# BMU_control.net
KiCad netlist of a schematic drawn in Altium Designer
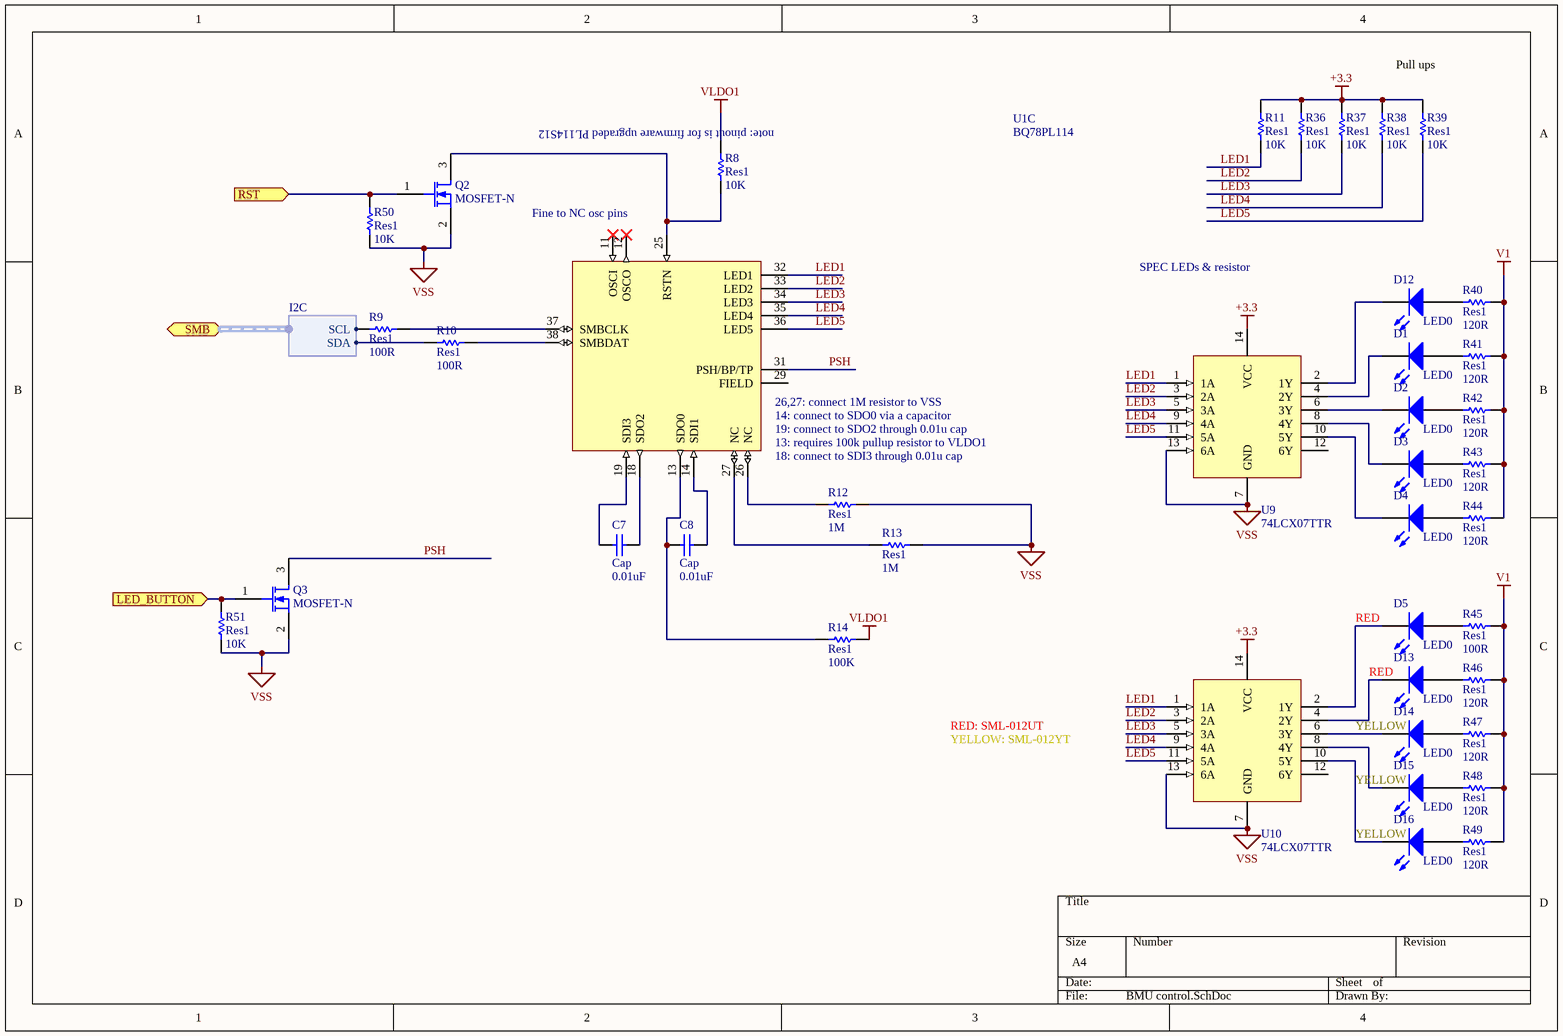
[diagram p0: BMU control.SchDoc]

(export (version "E")
  (design (tool "Eeschema 10.0.6"))
  (components
    (comp (ref "C7")
      (value "Cap")
      (footprint "C0805")
      (description "Capacitor")
      (fields (field (name "ALTIUM_VALUE") "0.01uF") (field (name "PUBLISHER") "Altium Limited"))
      (libsource (lib "Miscellaneous Devices") (part "Cap"))
    )
    (comp (ref "C8")
      (value "Cap")
      (footprint "C0805")
      (description "Capacitor")
      (fields (field (name "ALTIUM_VALUE") "0.01uF") (field (name "PUBLISHER") "Altium Limited"))
      (libsource (lib "Miscellaneous Devices") (part "Cap"))
    )
    (comp (ref "D1")
      (value "LED0")
      (footprint "SML-01 (ROHM LED SERIES)")
      (fields (field (name "PUBLISHER") "Altium Limited"))
      (libsource (lib "Miscellaneous Devices") (part "LED0"))
    )
    (comp (ref "D2")
      (value "LED0")
      (footprint "SML-01 (ROHM LED SERIES)")
      (fields (field (name "PUBLISHER") "Altium Limited"))
      (libsource (lib "Miscellaneous Devices") (part "LED0"))
    )
    (comp (ref "D3")
      (value "LED0")
      (footprint "SML-01 (ROHM LED SERIES)")
      (fields (field (name "PUBLISHER") "Altium Limited"))
      (libsource (lib "Miscellaneous Devices") (part "LED0"))
    )
    (comp (ref "D4")
      (value "LED0")
      (footprint "SML-01 (ROHM LED SERIES)")
      (fields (field (name "PUBLISHER") "Altium Limited"))
      (libsource (lib "Miscellaneous Devices") (part "LED0"))
    )
    (comp (ref "D5")
      (value "LED0")
      (footprint "SML-01 (ROHM LED SERIES)")
      (fields (field (name "COLOUR") "RED") (field (name "PUBLISHER") "Altium Limited"))
      (libsource (lib "Miscellaneous Devices") (part "LED0"))
    )
    (comp (ref "D12")
      (value "LED0")
      (footprint "SML-01 (ROHM LED SERIES)")
      (fields (field (name "PUBLISHER") "Altium Limited"))
      (libsource (lib "Miscellaneous Devices") (part "LED0"))
    )
    (comp (ref "D13")
      (value "LED0")
      (footprint "SML-01 (ROHM LED SERIES)")
      (fields (field (name "COLOUR") "RED") (field (name "PUBLISHER") "Altium Limited"))
      (libsource (lib "Miscellaneous Devices") (part "LED0"))
    )
    (comp (ref "D14")
      (value "LED0")
      (footprint "SML-01 (ROHM LED SERIES)")
      (fields (field (name "COLOUR") "YELLOW") (field (name "PUBLISHER") "Altium Limited"))
      (libsource (lib "Miscellaneous Devices") (part "LED0"))
    )
    (comp (ref "D15")
      (value "LED0")
      (footprint "SML-01 (ROHM LED SERIES)")
      (fields (field (name "COLOUR") "YELLOW") (field (name "PUBLISHER") "Altium Limited"))
      (libsource (lib "Miscellaneous Devices") (part "LED0"))
    )
    (comp (ref "D16")
      (value "LED0")
      (footprint "SML-01 (ROHM LED SERIES)")
      (fields (field (name "COLOUR") "YELLOW") (field (name "PUBLISHER") "Altium Limited"))
      (libsource (lib "Miscellaneous Devices") (part "LED0"))
    )
    (comp (ref "Q2")
      (value "MOSFET-N")
      (footprint "2N7002")
      (description "NXP - 2N7002 - MOSFET,N CH, 60V,0.3A,SOT23")
      (libsource (lib "2N7002") (part "2N7002"))
    )
    (comp (ref "Q3")
      (value "MOSFET-N")
      (footprint "2N7002")
      (description "NXP - 2N7002 - MOSFET,N CH, 60V,0.3A,SOT23")
      (libsource (lib "2N7002") (part "2N7002"))
    )
    (comp (ref "R8")
      (value "Res1")
      (footprint "R0603")
      (description "Resistor")
      (fields (field (name "ALTIUM_VALUE") "10K") (field (name "PUBLISHER") "Altium Limited"))
      (libsource (lib "Miscellaneous Devices") (part "Res1"))
    )
    (comp (ref "R9")
      (value "Res1")
      (footprint "R0603")
      (description "Resistor")
      (fields (field (name "ALTIUM_VALUE") "100R") (field (name "PUBLISHER") "Altium Limited"))
      (libsource (lib "Miscellaneous Devices") (part "Res1"))
    )
    (comp (ref "R10")
      (value "Res1")
      (footprint "R0603")
      (description "Resistor")
      (fields (field (name "ALTIUM_VALUE") "100R") (field (name "PUBLISHER") "Altium Limited"))
      (libsource (lib "Miscellaneous Devices") (part "Res1"))
    )
    (comp (ref "R11")
      (value "Res1")
      (footprint "R0603")
      (description "Resistor")
      (fields (field (name "ALTIUM_VALUE") "10K") (field (name "PUBLISHER") "Altium Limited"))
      (libsource (lib "Miscellaneous Devices") (part "Res1"))
    )
    (comp (ref "R12")
      (value "Res1")
      (footprint "R0603")
      (description "Resistor")
      (fields (field (name "ALTIUM_VALUE") "1M") (field (name "PUBLISHER") "Altium Limited"))
      (libsource (lib "Miscellaneous Devices") (part "Res1"))
    )
    (comp (ref "R13")
      (value "Res1")
      (footprint "R0603")
      (description "Resistor")
      (fields (field (name "ALTIUM_VALUE") "1M") (field (name "PUBLISHER") "Altium Limited"))
      (libsource (lib "Miscellaneous Devices") (part "Res1"))
    )
    (comp (ref "R14")
      (value "Res1")
      (footprint "R0603")
      (description "Resistor")
      (fields (field (name "ALTIUM_VALUE") "100K") (field (name "PUBLISHER") "Altium Limited"))
      (libsource (lib "Miscellaneous Devices") (part "Res1"))
    )
    (comp (ref "R36")
      (value "Res1")
      (footprint "R0603")
      (description "Resistor")
      (fields (field (name "ALTIUM_VALUE") "10K") (field (name "PUBLISHER") "Altium Limited"))
      (libsource (lib "Miscellaneous Devices") (part "Res1"))
    )
    (comp (ref "R37")
      (value "Res1")
      (footprint "R0603")
      (description "Resistor")
      (fields (field (name "ALTIUM_VALUE") "10K") (field (name "PUBLISHER") "Altium Limited"))
      (libsource (lib "Miscellaneous Devices") (part "Res1"))
    )
    (comp (ref "R38")
      (value "Res1")
      (footprint "R0603")
      (description "Resistor")
      (fields (field (name "ALTIUM_VALUE") "10K") (field (name "PUBLISHER") "Altium Limited"))
      (libsource (lib "Miscellaneous Devices") (part "Res1"))
    )
    (comp (ref "R39")
      (value "Res1")
      (footprint "R0603")
      (description "Resistor")
      (fields (field (name "ALTIUM_VALUE") "10K") (field (name "PUBLISHER") "Altium Limited"))
      (libsource (lib "Miscellaneous Devices") (part "Res1"))
    )
    (comp (ref "R40")
      (value "Res1")
      (footprint "R0603")
      (description "Resistor")
      (fields (field (name "ALTIUM_VALUE") "120R") (field (name "PUBLISHER") "Altium Limited"))
      (libsource (lib "Miscellaneous Devices") (part "Res1"))
    )
    (comp (ref "R41")
      (value "Res1")
      (footprint "R0603")
      (description "Resistor")
      (fields (field (name "ALTIUM_VALUE") "120R") (field (name "PUBLISHER") "Altium Limited"))
      (libsource (lib "Miscellaneous Devices") (part "Res1"))
    )
    (comp (ref "R42")
      (value "Res1")
      (footprint "R0603")
      (description "Resistor")
      (fields (field (name "ALTIUM_VALUE") "120R") (field (name "PUBLISHER") "Altium Limited"))
      (libsource (lib "Miscellaneous Devices") (part "Res1"))
    )
    (comp (ref "R43")
      (value "Res1")
      (footprint "R0603")
      (description "Resistor")
      (fields (field (name "ALTIUM_VALUE") "120R") (field (name "PUBLISHER") "Altium Limited"))
      (libsource (lib "Miscellaneous Devices") (part "Res1"))
    )
    (comp (ref "R44")
      (value "Res1")
      (footprint "R0603")
      (description "Resistor")
      (fields (field (name "ALTIUM_VALUE") "120R") (field (name "PUBLISHER") "Altium Limited"))
      (libsource (lib "Miscellaneous Devices") (part "Res1"))
    )
    (comp (ref "R45")
      (value "Res1")
      (footprint "R0603")
      (description "Resistor")
      (fields (field (name "ALTIUM_VALUE") "100R") (field (name "PUBLISHER") "Altium Limited"))
      (libsource (lib "Miscellaneous Devices") (part "Res1"))
    )
    (comp (ref "R46")
      (value "Res1")
      (footprint "R0603")
      (description "Resistor")
      (fields (field (name "ALTIUM_VALUE") "120R") (field (name "PUBLISHER") "Altium Limited"))
      (libsource (lib "Miscellaneous Devices") (part "Res1"))
    )
    (comp (ref "R47")
      (value "Res1")
      (footprint "R0603")
      (description "Resistor")
      (fields (field (name "ALTIUM_VALUE") "120R") (field (name "PUBLISHER") "Altium Limited"))
      (libsource (lib "Miscellaneous Devices") (part "Res1"))
    )
    (comp (ref "R48")
      (value "Res1")
      (footprint "R0603")
      (description "Resistor")
      (fields (field (name "ALTIUM_VALUE") "120R") (field (name "PUBLISHER") "Altium Limited"))
      (libsource (lib "Miscellaneous Devices") (part "Res1"))
    )
    (comp (ref "R49")
      (value "Res1")
      (footprint "R0603")
      (description "Resistor")
      (fields (field (name "ALTIUM_VALUE") "120R") (field (name "PUBLISHER") "Altium Limited"))
      (libsource (lib "Miscellaneous Devices") (part "Res1"))
    )
    (comp (ref "R50")
      (value "Res1")
      (footprint "R0603")
      (description "Resistor")
      (fields (field (name "ALTIUM_VALUE") "10K") (field (name "PUBLISHER") "Altium Limited"))
      (libsource (lib "Miscellaneous Devices") (part "Res1"))
    )
    (comp (ref "R51")
      (value "Res1")
      (footprint "R0603")
      (description "Resistor")
      (fields (field (name "ALTIUM_VALUE") "10K") (field (name "PUBLISHER") "Altium Limited"))
      (libsource (lib "Miscellaneous Devices") (part "Res1"))
    )
    (comp (ref "U1")
      (value "BQ78PL114")
      (footprint "QFN50P700X700X100-48N")
      (description "IC, BATT MANAGEMENT CONTRL, 48QFN")
      (libsource (lib "BQ78PL114") (part "BQ78PL114"))
    )
    (comp (ref "U9")
      (value "74LCX07TTR")
      (footprint "74LCX07TTR")
      (description "STMICROELECTRONICS - 74LCX07TTR - IC, HEX BUFFER, SMD, TSSOP14")
      (libsource (lib "74LCX07 (hex buffer)") (part "74LCX07TTR"))
    )
    (comp (ref "U10")
      (value "74LCX07TTR")
      (footprint "74LCX07TTR")
      (description "STMICROELECTRONICS - 74LCX07TTR - IC, HEX BUFFER, SMD, TSSOP14")
      (libsource (lib "74LCX07 (hex buffer)") (part "74LCX07TTR"))
    )
  )
  (nets
    (net (code "2") (name "+3.3") (class "Default")
      (node (ref "R11") (pin "2") (pinfunction "2_2") (pintype "passive"))
      (node (ref "R36") (pin "2") (pinfunction "2_2") (pintype "passive"))
      (node (ref "R37") (pin "2") (pinfunction "2_2") (pintype "passive"))
      (node (ref "R38") (pin "2") (pinfunction "2_2") (pintype "passive"))
      (node (ref "R39") (pin "2") (pinfunction "2_2") (pintype "passive"))
      (node (ref "U10") (pin "14") (pinfunction "VCC_14") (pintype "power_in"))
      (node (ref "U9") (pin "14") (pinfunction "VCC_14") (pintype "power_in"))
    )
    (net (code "3") (name "/LED1") (class "Default")
      (node (ref "R11") (pin "1") (pinfunction "1_1") (pintype "passive"))
      (node (ref "U1") (pin "32") (pinfunction "LED1_32") (pintype "open_emitter"))
      (node (ref "U10") (pin "1") (pinfunction "1A_1") (pintype "input"))
      (node (ref "U9") (pin "1") (pinfunction "1A_1") (pintype "input"))
    )
    (net (code "4") (name "/LED2") (class "Default")
      (node (ref "R36") (pin "1") (pinfunction "1_1") (pintype "passive"))
      (node (ref "U1") (pin "33") (pinfunction "LED2_33") (pintype "open_emitter"))
      (node (ref "U10") (pin "3") (pinfunction "2A_3") (pintype "input"))
      (node (ref "U9") (pin "3") (pinfunction "2A_3") (pintype "input"))
    )
    (net (code "5") (name "/LED3") (class "Default")
      (node (ref "R37") (pin "1") (pinfunction "1_1") (pintype "passive"))
      (node (ref "U1") (pin "34") (pinfunction "LED3_34") (pintype "open_emitter"))
      (node (ref "U10") (pin "5") (pinfunction "3A_5") (pintype "input"))
      (node (ref "U9") (pin "5") (pinfunction "3A_5") (pintype "input"))
    )
    (net (code "6") (name "/LED4") (class "Default")
      (node (ref "R38") (pin "1") (pinfunction "1_1") (pintype "passive"))
      (node (ref "U1") (pin "35") (pinfunction "LED4_35") (pintype "open_emitter"))
      (node (ref "U10") (pin "9") (pinfunction "4A_9") (pintype "input"))
      (node (ref "U9") (pin "9") (pinfunction "4A_9") (pintype "input"))
    )
    (net (code "7") (name "/LED5") (class "Default")
      (node (ref "R39") (pin "1") (pinfunction "1_1") (pintype "passive"))
      (node (ref "U1") (pin "36") (pinfunction "LED5_36") (pintype "open_emitter"))
      (node (ref "U10") (pin "11") (pinfunction "5A_11") (pintype "input"))
      (node (ref "U9") (pin "11") (pinfunction "5A_11") (pintype "input"))
    )
    (net (code "8") (name "/LED_BUTTON") (class "Default")
      (node (ref "Q3") (pin "1") (pinfunction "G_1") (pintype "passive"))
      (node (ref "R51") (pin "2") (pinfunction "2_2") (pintype "passive"))
    )
    (net (code "9") (name "/PSH") (class "Default")
      (node (ref "Q3") (pin "3") (pinfunction "D_3") (pintype "passive"))
      (node (ref "U1") (pin "31") (pinfunction "PSH/BP/TP_31") (pintype "passive"))
    )
    (net (code "10") (name "/RST") (class "Default")
      (node (ref "Q2") (pin "1") (pinfunction "G_1") (pintype "passive"))
      (node (ref "R50") (pin "2") (pinfunction "2_2") (pintype "passive"))
    )
    (net (code "11") (name "/SCL") (class "Default")
      (node (ref "R9") (pin "1") (pinfunction "1_1") (pintype "passive"))
    )
    (net (code "12") (name "/SDA") (class "Default")
      (node (ref "R10") (pin "1") (pinfunction "1_1") (pintype "passive"))
    )
    (net (code "14") (name "Net-(D1-A)") (class "Default")
      (node (ref "D1") (pin "1") (pinfunction "A_1") (pintype "passive"))
      (node (ref "R41") (pin "2") (pinfunction "2_2") (pintype "passive"))
    )
    (net (code "15") (name "Net-(D1-K)") (class "Default")
      (node (ref "D1") (pin "2") (pinfunction "K_2") (pintype "passive"))
      (node (ref "U9") (pin "4") (pinfunction "2Y_4") (pintype "open_collector"))
    )
    (net (code "16") (name "Net-(D2-A)") (class "Default")
      (node (ref "D2") (pin "1") (pinfunction "A_1") (pintype "passive"))
      (node (ref "R42") (pin "2") (pinfunction "2_2") (pintype "passive"))
    )
    (net (code "17") (name "Net-(D2-K)") (class "Default")
      (node (ref "D2") (pin "2") (pinfunction "K_2") (pintype "passive"))
      (node (ref "U9") (pin "6") (pinfunction "3Y_6") (pintype "open_collector"))
    )
    (net (code "18") (name "Net-(D3-A)") (class "Default")
      (node (ref "D3") (pin "1") (pinfunction "A_1") (pintype "passive"))
      (node (ref "R43") (pin "2") (pinfunction "2_2") (pintype "passive"))
    )
    (net (code "19") (name "Net-(D3-K)") (class "Default")
      (node (ref "D3") (pin "2") (pinfunction "K_2") (pintype "passive"))
      (node (ref "U9") (pin "8") (pinfunction "4Y_8") (pintype "open_collector"))
    )
    (net (code "20") (name "Net-(D4-A)") (class "Default")
      (node (ref "D4") (pin "1") (pinfunction "A_1") (pintype "passive"))
      (node (ref "R44") (pin "2") (pinfunction "2_2") (pintype "passive"))
    )
    (net (code "21") (name "Net-(D4-K)") (class "Default")
      (node (ref "D4") (pin "2") (pinfunction "K_2") (pintype "passive"))
      (node (ref "U9") (pin "10") (pinfunction "5Y_10") (pintype "open_collector"))
    )
    (net (code "22") (name "Net-(D5-A)") (class "Default")
      (node (ref "D5") (pin "1") (pinfunction "A_1") (pintype "passive"))
      (node (ref "R45") (pin "2") (pinfunction "2_2") (pintype "passive"))
    )
    (net (code "23") (name "Net-(D5-K)") (class "Default")
      (node (ref "D5") (pin "2") (pinfunction "K_2") (pintype "passive"))
      (node (ref "U10") (pin "2") (pinfunction "1Y_2") (pintype "open_collector"))
    )
    (net (code "24") (name "Net-(D12-A)") (class "Default")
      (node (ref "D12") (pin "1") (pinfunction "A_1") (pintype "passive"))
      (node (ref "R40") (pin "2") (pinfunction "2_2") (pintype "passive"))
    )
    (net (code "25") (name "Net-(D12-K)") (class "Default")
      (node (ref "D12") (pin "2") (pinfunction "K_2") (pintype "passive"))
      (node (ref "U9") (pin "2") (pinfunction "1Y_2") (pintype "open_collector"))
    )
    (net (code "26") (name "Net-(D13-A)") (class "Default")
      (node (ref "D13") (pin "1") (pinfunction "A_1") (pintype "passive"))
      (node (ref "R46") (pin "2") (pinfunction "2_2") (pintype "passive"))
    )
    (net (code "27") (name "Net-(D13-K)") (class "Default")
      (node (ref "D13") (pin "2") (pinfunction "K_2") (pintype "passive"))
      (node (ref "U10") (pin "4") (pinfunction "2Y_4") (pintype "open_collector"))
    )
    (net (code "28") (name "Net-(D14-A)") (class "Default")
      (node (ref "D14") (pin "1") (pinfunction "A_1") (pintype "passive"))
      (node (ref "R47") (pin "2") (pinfunction "2_2") (pintype "passive"))
    )
    (net (code "29") (name "Net-(D14-K)") (class "Default")
      (node (ref "D14") (pin "2") (pinfunction "K_2") (pintype "passive"))
      (node (ref "U10") (pin "6") (pinfunction "3Y_6") (pintype "open_collector"))
    )
    (net (code "30") (name "Net-(D15-A)") (class "Default")
      (node (ref "D15") (pin "1") (pinfunction "A_1") (pintype "passive"))
      (node (ref "R48") (pin "2") (pinfunction "2_2") (pintype "passive"))
    )
    (net (code "31") (name "Net-(D15-K)") (class "Default")
      (node (ref "D15") (pin "2") (pinfunction "K_2") (pintype "passive"))
      (node (ref "U10") (pin "8") (pinfunction "4Y_8") (pintype "open_collector"))
    )
    (net (code "32") (name "Net-(D16-A)") (class "Default")
      (node (ref "D16") (pin "1") (pinfunction "A_1") (pintype "passive"))
      (node (ref "R49") (pin "2") (pinfunction "2_2") (pintype "passive"))
    )
    (net (code "33") (name "Net-(D16-K)") (class "Default")
      (node (ref "D16") (pin "2") (pinfunction "K_2") (pintype "passive"))
      (node (ref "U10") (pin "10") (pinfunction "5Y_10") (pintype "open_collector"))
    )
    (net (code "34") (name "Net-(Q2-D)") (class "Default")
      (node (ref "Q2") (pin "3") (pinfunction "D_3") (pintype "passive"))
      (node (ref "R8") (pin "2") (pinfunction "2_2") (pintype "passive"))
      (node (ref "U1") (pin "25") (pinfunction "RSTN_25") (pintype "input"))
    )
    (net (code "35") (name "Net-(R12-Pad1)") (class "Default")
      (node (ref "R12") (pin "1") (pinfunction "1_1") (pintype "passive"))
      (node (ref "U1") (pin "26") (pinfunction "NC_26") (pintype "bidirectional"))
    )
    (net (code "36") (name "Net-(R13-Pad1)") (class "Default")
      (node (ref "R13") (pin "1") (pinfunction "1_1") (pintype "passive"))
      (node (ref "U1") (pin "27") (pinfunction "NC_27") (pintype "bidirectional"))
    )
    (net (code "37") (name "Net-(U1C-SDI1)") (class "Default")
      (node (ref "C8") (pin "2") (pinfunction "2_2") (pintype "passive"))
      (node (ref "U1") (pin "14") (pinfunction "SDI1_14") (pintype "input"))
    )
    (net (code "38") (name "Net-(U1C-SDI3)") (class "Default")
      (node (ref "C7") (pin "1") (pinfunction "1_1") (pintype "passive"))
      (node (ref "U1") (pin "19") (pinfunction "SDI3_19") (pintype "input"))
    )
    (net (code "39") (name "Net-(U1C-SDO0)") (class "Default")
      (node (ref "C8") (pin "1") (pinfunction "1_1") (pintype "passive"))
      (node (ref "R14") (pin "1") (pinfunction "1_1") (pintype "passive"))
      (node (ref "U1") (pin "13") (pinfunction "SDO0_13") (pintype "output"))
    )
    (net (code "40") (name "Net-(U1C-SDO2)") (class "Default")
      (node (ref "C7") (pin "2") (pinfunction "2_2") (pintype "passive"))
      (node (ref "U1") (pin "18") (pinfunction "SDO2_18") (pintype "output"))
    )
    (net (code "41") (name "Net-(U1C-SMBCLK)") (class "Default")
      (node (ref "R9") (pin "2") (pinfunction "2_2") (pintype "passive"))
      (node (ref "U1") (pin "37") (pinfunction "SMBCLK_37") (pintype "bidirectional"))
    )
    (net (code "42") (name "Net-(U1C-SMBDAT)") (class "Default")
      (node (ref "R10") (pin "2") (pinfunction "2_2") (pintype "passive"))
      (node (ref "U1") (pin "38") (pinfunction "SMBDAT_38") (pintype "bidirectional"))
    )
    (net (code "43") (name "V1") (class "Default")
      (node (ref "R40") (pin "1") (pinfunction "1_1") (pintype "passive"))
      (node (ref "R41") (pin "1") (pinfunction "1_1") (pintype "passive"))
      (node (ref "R42") (pin "1") (pinfunction "1_1") (pintype "passive"))
      (node (ref "R43") (pin "1") (pinfunction "1_1") (pintype "passive"))
      (node (ref "R44") (pin "1") (pinfunction "1_1") (pintype "passive"))
      (node (ref "R45") (pin "1") (pinfunction "1_1") (pintype "passive"))
      (node (ref "R46") (pin "1") (pinfunction "1_1") (pintype "passive"))
      (node (ref "R47") (pin "1") (pinfunction "1_1") (pintype "passive"))
      (node (ref "R48") (pin "1") (pinfunction "1_1") (pintype "passive"))
      (node (ref "R49") (pin "1") (pinfunction "1_1") (pintype "passive"))
    )
    (net (code "44") (name "VLDO1") (class "Default")
      (node (ref "R14") (pin "2") (pinfunction "2_2") (pintype "passive"))
      (node (ref "R8") (pin "1") (pinfunction "1_1") (pintype "passive"))
    )
    (net (code "45") (name "VSS") (class "Default")
      (node (ref "Q2") (pin "2") (pinfunction "S_2") (pintype "passive"))
      (node (ref "Q3") (pin "2") (pinfunction "S_2") (pintype "passive"))
      (node (ref "R12") (pin "2") (pinfunction "2_2") (pintype "passive"))
      (node (ref "R13") (pin "2") (pinfunction "2_2") (pintype "passive"))
      (node (ref "R50") (pin "1") (pinfunction "1_1") (pintype "passive"))
      (node (ref "R51") (pin "1") (pinfunction "1_1") (pintype "passive"))
      (node (ref "U10") (pin "13") (pinfunction "6A_13") (pintype "input"))
      (node (ref "U10") (pin "7") (pinfunction "GND_7") (pintype "power_in"))
      (node (ref "U9") (pin "13") (pinfunction "6A_13") (pintype "input"))
      (node (ref "U9") (pin "7") (pinfunction "GND_7") (pintype "power_in"))
    )
    (net (code "46") (name "unconnected-(U1C-FIELD-Pad29)") (class "Default")
      (node (ref "U1") (pin "29") (pinfunction "FIELD_29") (pintype "passive"))
    )
    (net (code "47") (name "unconnected-(U1C-OSCI-Pad11)") (class "Default")
      (node (ref "U1") (pin "11") (pinfunction "OSCI_11") (pintype "input+no_connect"))
    )
    (net (code "48") (name "unconnected-(U1C-OSCO-Pad12)") (class "Default")
      (node (ref "U1") (pin "12") (pinfunction "OSCO_12") (pintype "output+no_connect"))
    )
    (net (code "49") (name "unconnected-(U9-6Y-Pad12)") (class "Default")
      (node (ref "U9") (pin "12") (pinfunction "6Y_12") (pintype "open_collector"))
    )
    (net (code "50") (name "unconnected-(U10-6Y-Pad12)") (class "Default")
      (node (ref "U10") (pin "12") (pinfunction "6Y_12") (pintype "open_collector"))
    )
  )
)
